# SCK_DATA_BOARD_2_1.net
KiCad netlist of a schematic drawn in EAGLE
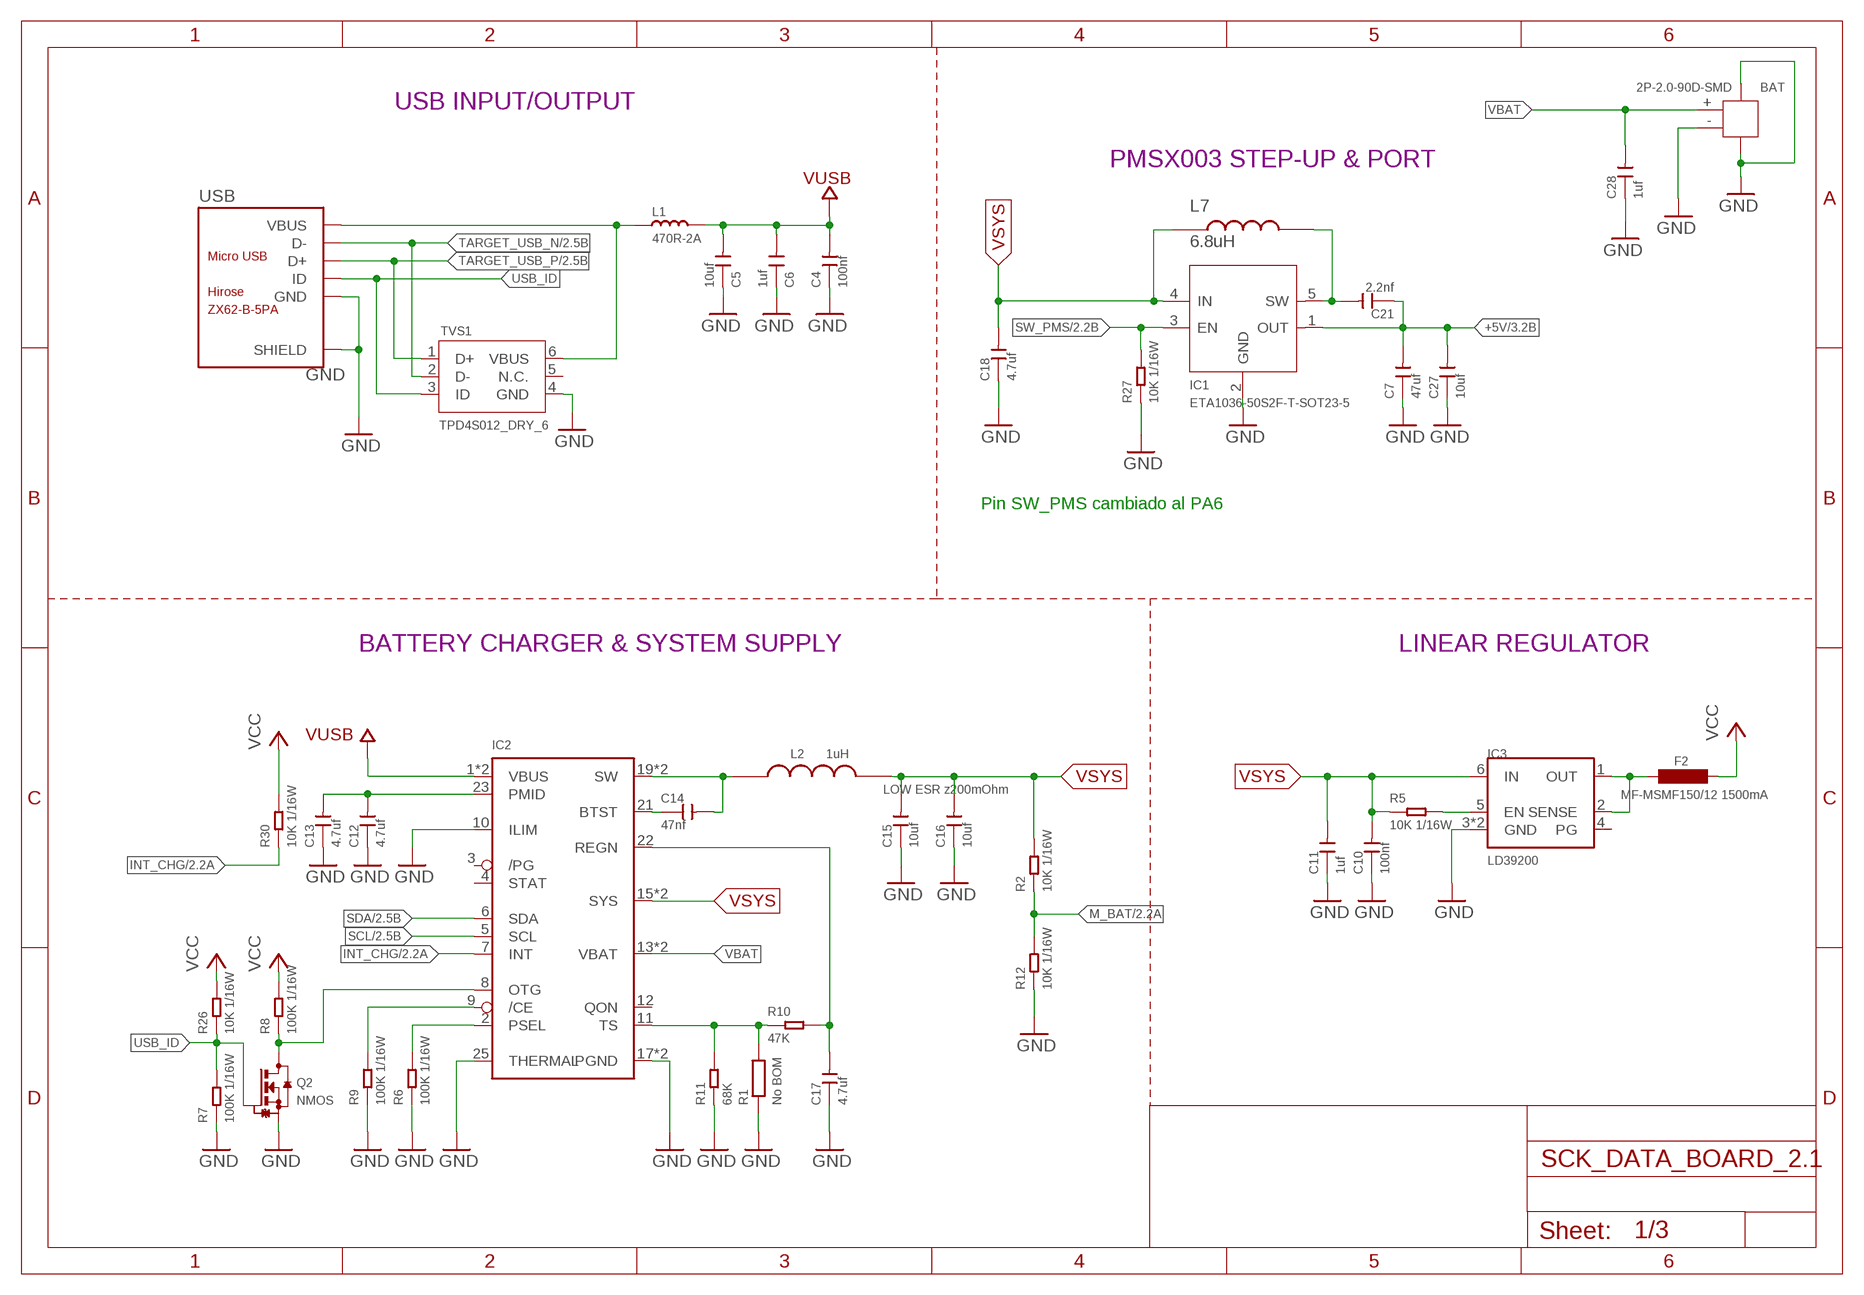
[diagram p0: schematic, sheet 1]
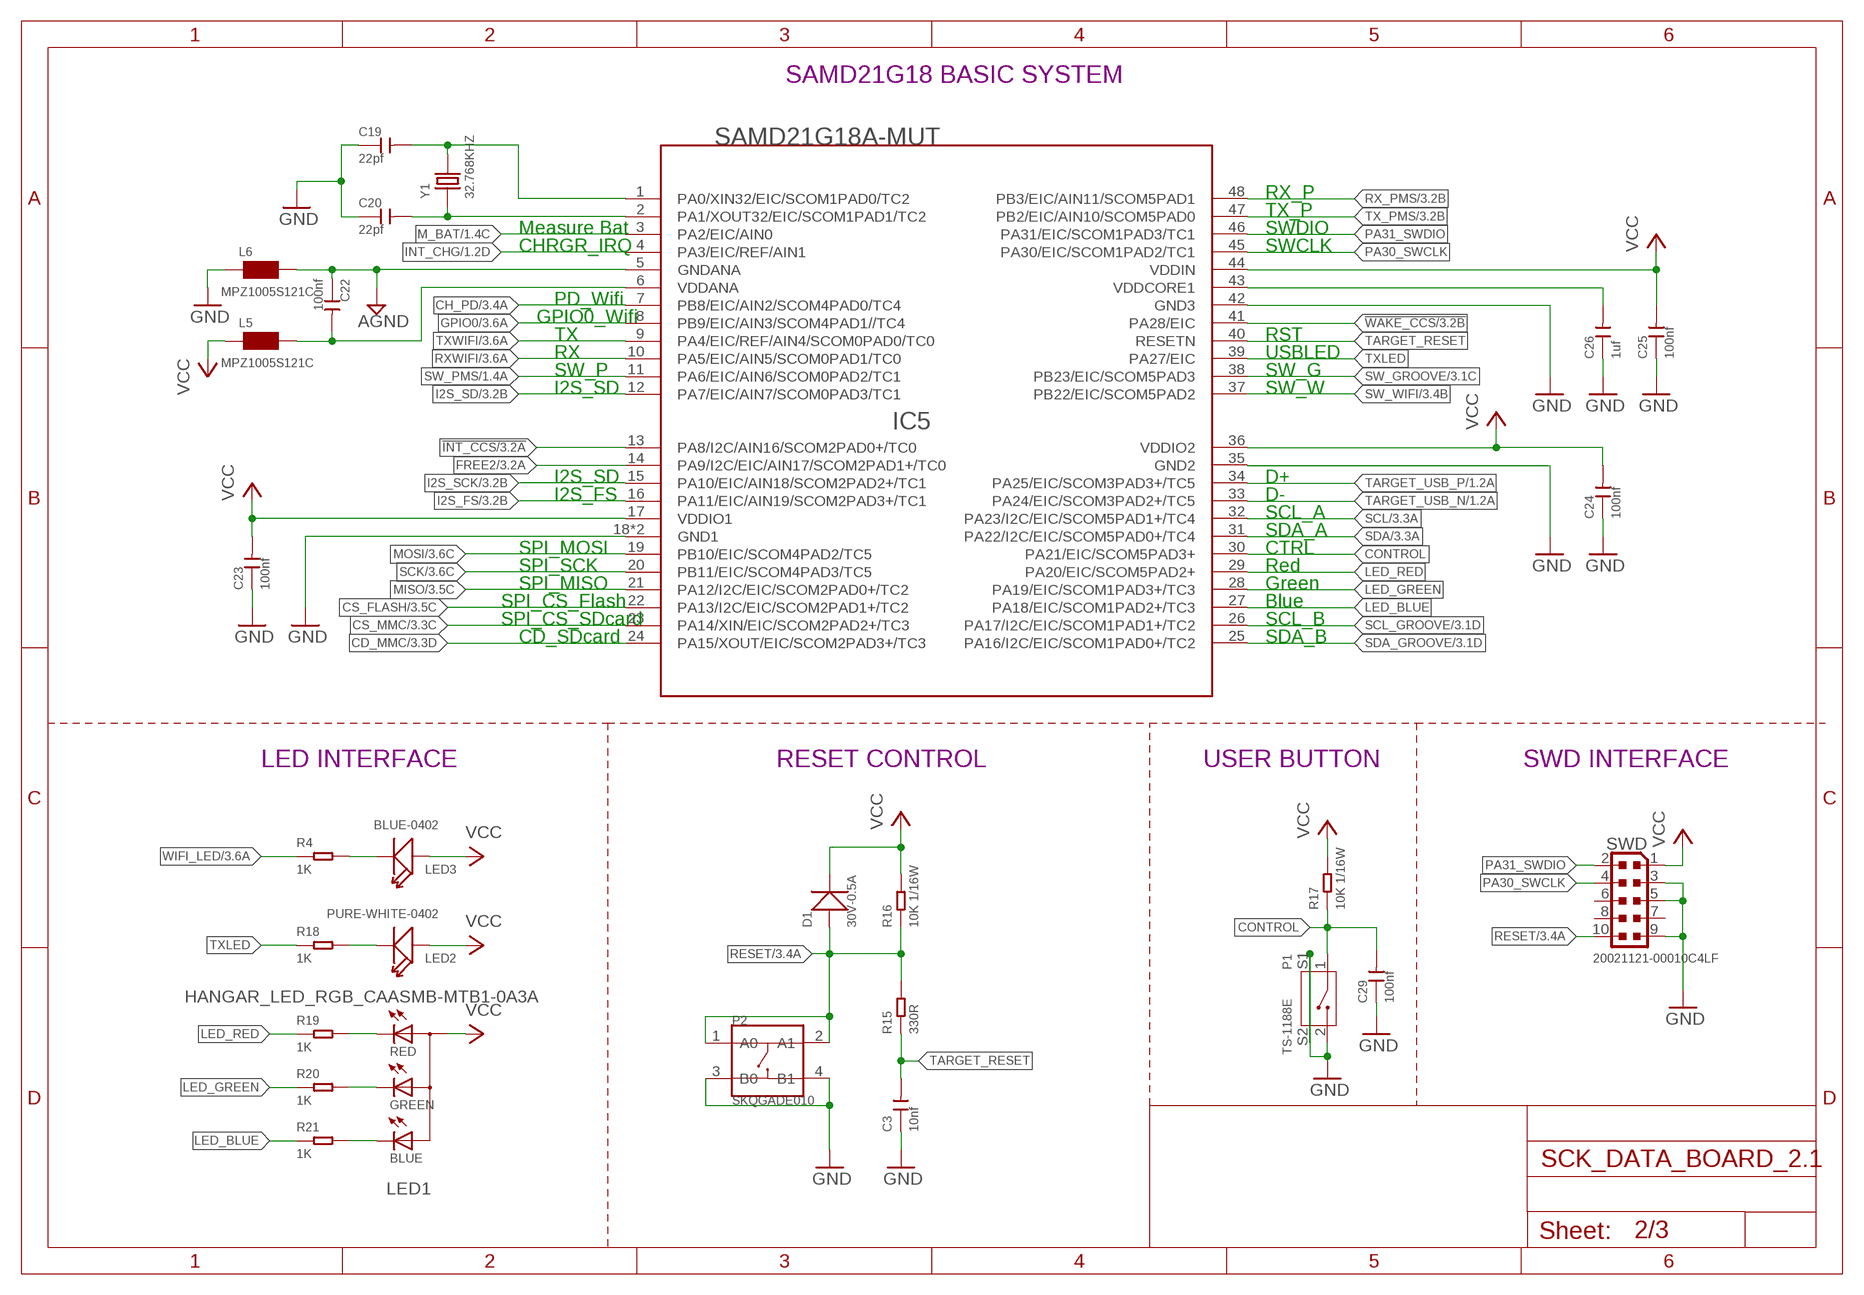
[diagram p1: schematic, sheet 2]
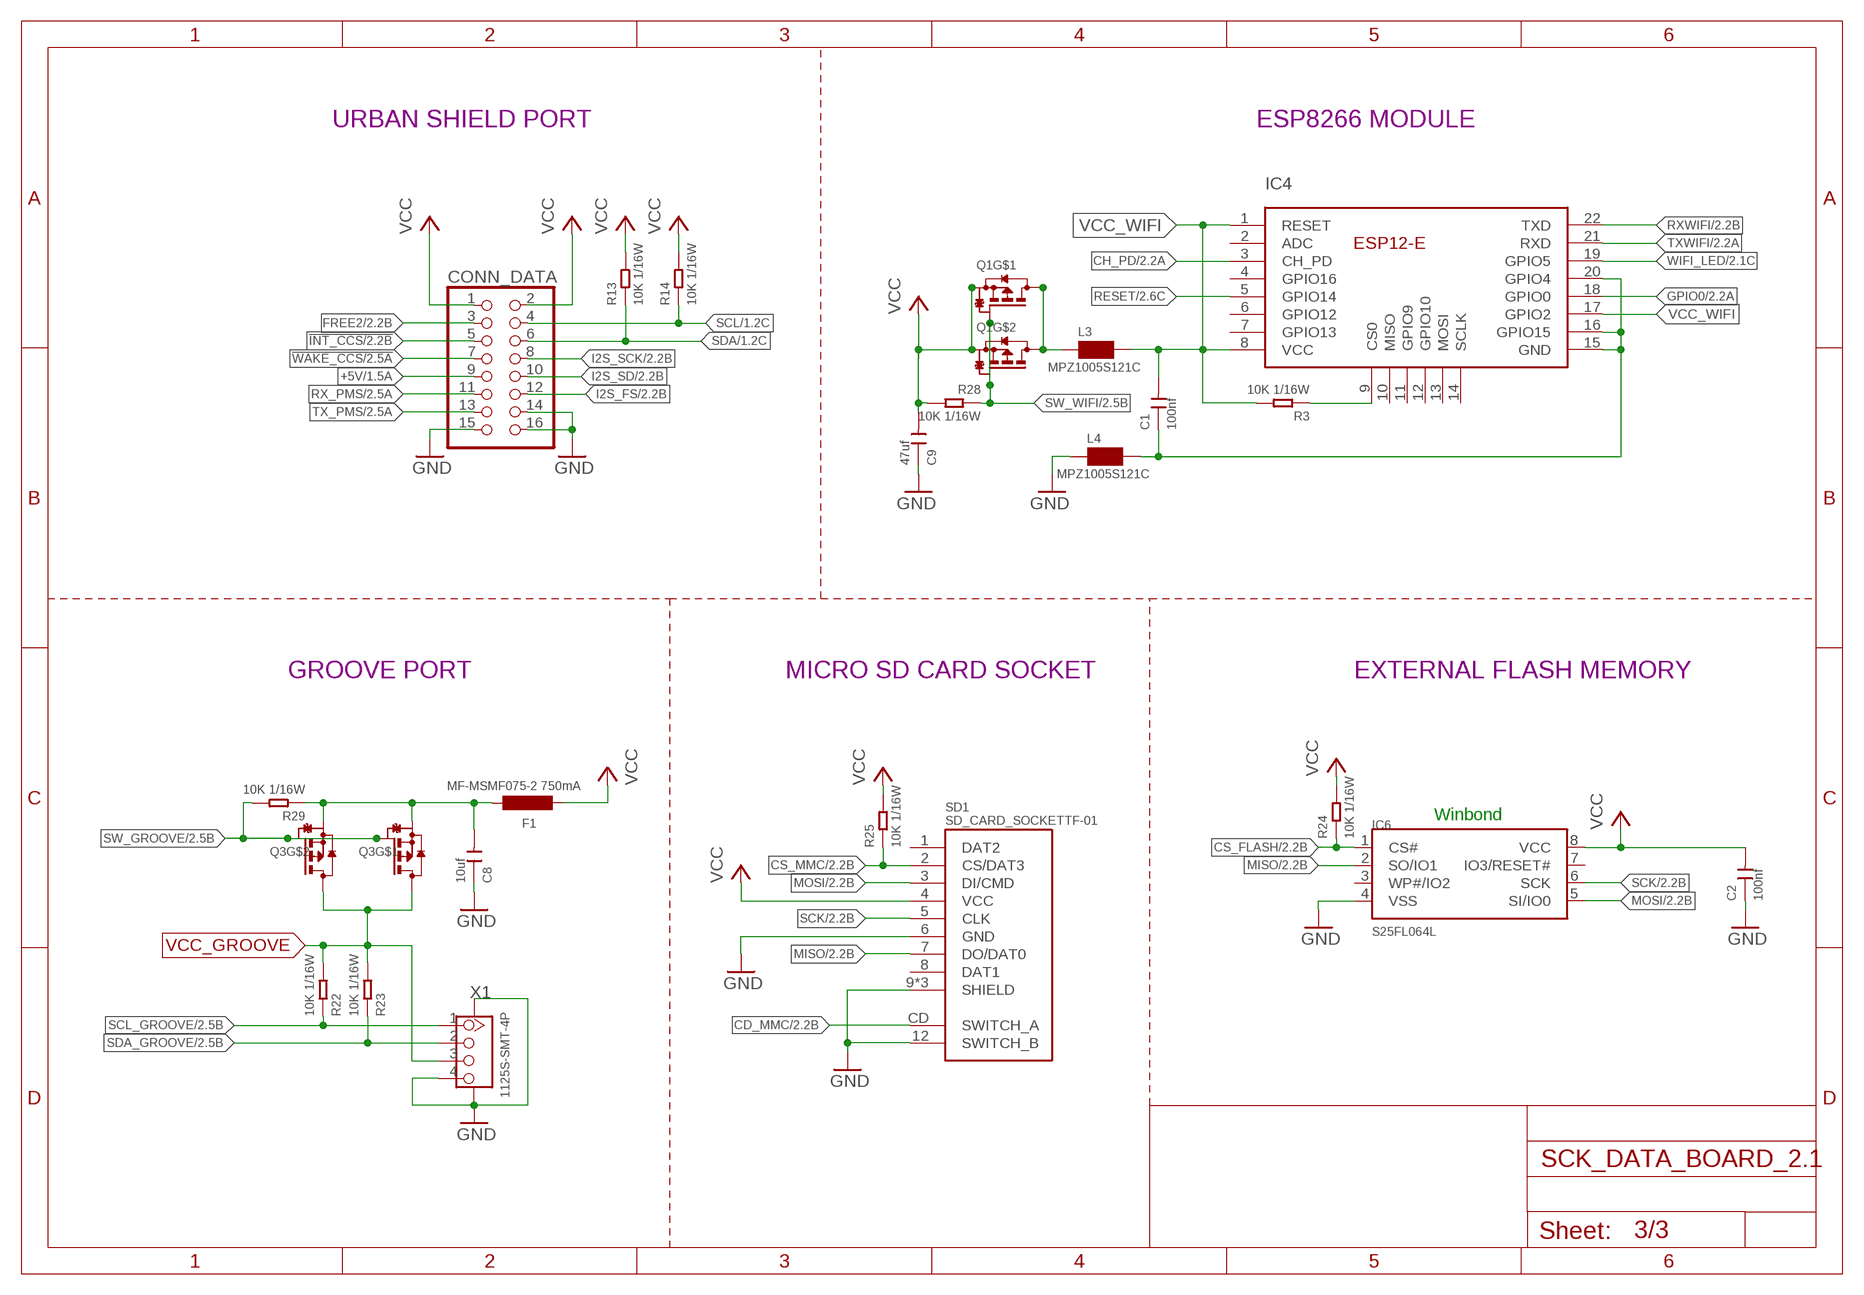
[diagram p2: schematic, sheet 3]

(export (version "E")
  (design (tool "Eeschema 10.0.6"))
  (components
    (comp (ref "BAT")
      (value "2P-2.0-90D-SMD")
      (footprint "eagle-import:HW2-SMD-2.0-90D")
      (libsource (lib "eagle-import") (part "CONN-HEADER-SMD-PH-SIDE-(2P-2.0MM)"))
    )
    (comp (ref "C4")
      (value "100nf")
      (footprint "eagle-import:C0402")
      (fields (field (name "MPN") "CC0402KRX7R8BB104"))
      (libsource (lib "eagle-import") (part "CERAMIC-100NF-25V-10%-X7R(0402)"))
    )
    (comp (ref "C5")
      (value "10uf")
      (footprint "eagle-import:C1206")
      (fields (field (name "MPN") "CC1206KKX5R8BB106"))
      (libsource (lib "eagle-import") (part "CERAMIC-10UF-25V-10%-X5R(1206)"))
    )
    (comp (ref "C6")
      (value "1uf")
      (footprint "eagle-import:C0805")
      (fields (field (name "MPN") "CC0805KKX7R8BB105"))
      (libsource (lib "eagle-import") (part "CERAMIC-1UF-25V-10%-X7R(0805)"))
    )
    (comp (ref "C7")
      (value "47uf")
      (footprint "eagle-import:C0805")
      (fields (field (name "MPN") "CC0805MKX5R5BB476"))
      (libsource (lib "eagle-import") (part "CERAMIC-47UF-6.3V-20%-X5R(0805)"))
    )
    (comp (ref "C10")
      (value "100nf")
      (footprint "eagle-import:C0402")
      (fields (field (name "MPN") "CC0402KRX7R8BB104"))
      (libsource (lib "eagle-import") (part "CERAMIC-100NF-25V-10%-X7R(0402)"))
    )
    (comp (ref "C11")
      (value "1uf")
      (footprint "eagle-import:C0805")
      (fields (field (name "MPN") "CC0805KKX7R8BB105"))
      (libsource (lib "eagle-import") (part "CERAMIC-1UF-25V-10%-X7R(0805)"))
    )
    (comp (ref "C12")
      (value "4.7uf")
      (footprint "eagle-import:C0603")
      (fields (field (name "MPN") "CC0603KRX5R6BB475"))
      (libsource (lib "eagle-import") (part "CERAMIC-4.7UF-10V-10%-X5R(0603)"))
    )
    (comp (ref "C13")
      (value "4.7uf")
      (footprint "eagle-import:C0603")
      (fields (field (name "MPN") "CC0603KRX5R6BB475"))
      (libsource (lib "eagle-import") (part "CERAMIC-4.7UF-10V-10%-X5R(0603)"))
    )
    (comp (ref "C14")
      (value "47nf")
      (footprint "eagle-import:C0402")
      (fields (field (name "MPN") "CC0402KRX7R8BB473"))
      (libsource (lib "eagle-import") (part "CERAMIC-47NF-25V-10%-X7R(0402)"))
    )
    (comp (ref "C15")
      (value "10uf")
      (footprint "eagle-import:C0603")
      (fields (field (name "MPN") "CC0603KRX5R6BB106"))
      (libsource (lib "eagle-import") (part "Seeed-OPL-Capacitor_CERAMIC-10UF-10V-10%-X5R(0603)"))
    )
    (comp (ref "C16")
      (value "10uf")
      (footprint "eagle-import:C0603")
      (fields (field (name "MPN") "CC0603KRX5R6BB106"))
      (libsource (lib "eagle-import") (part "Seeed-OPL-Capacitor_CERAMIC-10UF-10V-10%-X5R(0603)"))
    )
    (comp (ref "C17")
      (value "4.7uf")
      (footprint "eagle-import:C0603")
      (fields (field (name "MPN") "CC0603KRX5R6BB475"))
      (libsource (lib "eagle-import") (part "CERAMIC-4.7UF-10V-10%-X5R(0603)"))
    )
    (comp (ref "C18")
      (value "4.7uf")
      (footprint "eagle-import:C0603")
      (fields (field (name "MPN") "CC0603KRX5R6BB475"))
      (libsource (lib "eagle-import") (part "CERAMIC-4.7UF-10V-10%-X5R(0603)"))
    )
    (comp (ref "C21")
      (value "2.2nf")
      (footprint "eagle-import:C0402")
      (fields (field (name "MPN") "CC0402KRX7R9BB222"))
      (libsource (lib "eagle-import") (part "CERAMIC-2.2NF-50V-10%-X7R(0402)"))
    )
    (comp (ref "C27")
      (value "10uf")
      (footprint "eagle-import:C0603")
      (fields (field (name "MPN") "CC0603KRX5R6BB106"))
      (libsource (lib "eagle-import") (part "CERAMIC-10UF-10V-10%-X5R(0603)"))
    )
    (comp (ref "C28")
      (value "1uf")
      (footprint "eagle-import:C0805")
      (fields (field (name "MPN") "CC0805KKX7R8BB105"))
      (libsource (lib "eagle-import") (part "CERAMIC-1UF-25V-10%-X7R(0805)"))
    )
    (comp (ref "F2")
      (value "MF-MSMF150/12 1500mA")
      (footprint "eagle-import:L1812")
      (libsource (lib "eagle-import") (part "L-EUL1812"))
    )
    (comp (ref "IC1")
      (value "ETA1036-50S2F-T-SOT23-5")
      (footprint "eagle-import:SOT-23-5")
      (fields (field (name "MPN") "ETA1036-50S2F-T"))
      (libsource (lib "eagle-import") (part "PMIC-ETA1036-50S2F-T(SOT23-5)"))
    )
    (comp (ref "IC2")
      (value "BQ24259_VQFN(24)")
      (footprint "eagle-import:24-PIN_VQFN_THPAD")
      (libsource (lib "eagle-import") (part "BQ24259_VQFN(24)"))
    )
    (comp (ref "IC3")
      (value "LD39200")
      (footprint "eagle-import:DFN6_3X3MM")
      (libsource (lib "eagle-import") (part "LD39200"))
    )
    (comp (ref "L1")
      (value "470R-2A")
      (footprint "eagle-import:L0805")
      (fields (field (name "MPN") "WLB2012-471T20"))
      (libsource (lib "eagle-import") (part "SMD-FERRITE-BEAD-470R-2A(0805)'0805'"))
    )
    (comp (ref "L2")
      (value "1uH")
      (footprint "eagle-import:HANGAR_C1210")
      (libsource (lib "eagle-import") (part "LQH32PN1R0NNCL"))
    )
    (comp (ref "L7")
      (value "6.8uH")
      (footprint "eagle-import:IND_BOURNS_SRN3015TA_3X3_SMD")
      (libsource (lib "eagle-import") (part "RCL_L_SMD_SRN3015TA-6R8M"))
    )
    (comp (ref "Q2")
      (value "NMOS")
      (footprint "eagle-import:NMOS_UMT3")
      (libsource (lib "eagle-import") (part "NMOS_RJU003N03FRAT106"))
    )
    (comp (ref "R1")
      (value "No BOM")
      (footprint "eagle-import:HANGAR_R0402")
      (libsource (lib "eagle-import") (part "HANGAR_R-EU_R0402"))
    )
    (comp (ref "R2")
      (value "10K 1/16W")
      (footprint "eagle-import:R0402")
      (fields (field (name "MPN") "RC0402FR-0710KL"))
      (libsource (lib "eagle-import") (part "SMD-RES-10K-1%-1/16W(0402)"))
    )
    (comp (ref "R5")
      (value "10K 1/16W")
      (footprint "eagle-import:R0402")
      (fields (field (name "MPN") "RC0402FR-0710KL"))
      (libsource (lib "eagle-import") (part "SMD-RES-10K-1%-1/16W(0402)"))
    )
    (comp (ref "R6")
      (value "100K 1/16W")
      (footprint "eagle-import:R0402")
      (fields (field (name "MPN") "RC0402JR-07100KL"))
      (libsource (lib "eagle-import") (part "SMD-RES-100K-5%-1/16W(0402)"))
    )
    (comp (ref "R7")
      (value "100K 1/16W")
      (footprint "eagle-import:R0402")
      (fields (field (name "MPN") "RC0402JR-07100KL"))
      (libsource (lib "eagle-import") (part "SMD-RES-100K-5%-1/16W(0402)"))
    )
    (comp (ref "R8")
      (value "100K 1/16W")
      (footprint "eagle-import:R0402")
      (fields (field (name "MPN") "RC0402JR-07100KL"))
      (libsource (lib "eagle-import") (part "SMD-RES-100K-5%-1/16W(0402)"))
    )
    (comp (ref "R9")
      (value "100K 1/16W")
      (footprint "eagle-import:R0402")
      (fields (field (name "MPN") "RC0402JR-07100KL"))
      (libsource (lib "eagle-import") (part "SMD-RES-100K-5%-1/16W(0402)"))
    )
    (comp (ref "R10")
      (value "47K")
      (footprint "eagle-import:R0402")
      (fields (field (name "MPN") "RC0402JR-0747KL"))
      (libsource (lib "eagle-import") (part "SMD-RES-47K-5%-1/16W(0402)"))
    )
    (comp (ref "R11")
      (value "68K")
      (footprint "eagle-import:R0402")
      (fields (field (name "MPN") "RC0402JR-0768KL"))
      (libsource (lib "eagle-import") (part "SMD-RES-68K-50V-5%(0402)"))
    )
    (comp (ref "R12")
      (value "10K 1/16W")
      (footprint "eagle-import:R0402")
      (fields (field (name "MPN") "RC0402FR-0710KL"))
      (libsource (lib "eagle-import") (part "SMD-RES-10K-1%-1/16W(0402)"))
    )
    (comp (ref "R26")
      (value "10K 1/16W")
      (footprint "eagle-import:R0402")
      (fields (field (name "MPN") "RC0402FR-0710KL"))
      (libsource (lib "eagle-import") (part "SMD-RES-10K-1%-1/16W(0402)"))
    )
    (comp (ref "R27")
      (value "10K 1/16W")
      (footprint "eagle-import:R0402")
      (fields (field (name "MPN") "RC0402FR-0710KL"))
      (libsource (lib "eagle-import") (part "Seeed-Resistor_SMD-RES-10K-1%-1/16W(0402)"))
    )
    (comp (ref "R30")
      (value "10K 1/16W")
      (footprint "eagle-import:R0402")
      (fields (field (name "MPN") "RC0402FR-0710KL"))
      (libsource (lib "eagle-import") (part "SMD-RES-10K-1%-1/16W(0402)"))
    )
    (comp (ref "TVS1")
      (value "TPD4S012_DRY_6")
      (footprint "eagle-import:DRY6")
      (libsource (lib "eagle-import") (part "TPD4S012_DRY_6"))
    )
    (comp (ref "USB")
      (value "ZX62-B-5PA")
      (footprint "eagle-import:MICRO-USB5+6P-SMD-0.65-AB")
      (libsource (lib "eagle-import") (part "MICRO-USB-SMD(ZX62-B-5PA)"))
    )
    (comp (ref "C1")
      (value "100nf")
      (footprint "eagle-import:C0402")
      (fields (field (name "MPN") "CC0402KRX7R8BB104"))
      (libsource (lib "eagle-import") (part "CERAMIC-100NF-25V-10%-X7R(0402)"))
    )
    (comp (ref "C2")
      (value "100nf")
      (footprint "eagle-import:C0402")
      (fields (field (name "MPN") "CC0402KRX7R8BB104"))
      (libsource (lib "eagle-import") (part "CERAMIC-100NF-25V-10%-X7R(0402)"))
    )
    (comp (ref "C8")
      (value "10uf")
      (footprint "eagle-import:C1206")
      (fields (field (name "MPN") "CC1206KKX5R8BB106"))
      (libsource (lib "eagle-import") (part "CERAMIC-10UF-25V-10%-X5R(1206)"))
    )
    (comp (ref "C9")
      (value "47uf")
      (footprint "eagle-import:C1210")
      (fields (field (name "MPN") "GRM32ER71A476ME15L"))
      (libsource (lib "eagle-import") (part "CERAMIC-47UF-10V-20%-X7R(1210)"))
    )
    (comp (ref "CONN_DATA")
      (value "PINHD_2X8FEM_SMD")
      (footprint "eagle-import:PINHD_2X8_SMD_FEMALE_UNHOLED")
      (libsource (lib "eagle-import") (part "PINHD_2X8FEM_SMD"))
    )
    (comp (ref "F1")
      (value "MF-MSMF075-2 750mA")
      (footprint "eagle-import:L1812")
      (libsource (lib "eagle-import") (part "L-EUL1812"))
    )
    (comp (ref "IC4")
      (value "HANGAR_ESP-12-E")
      (footprint "eagle-import:HANGAR_ESP12-E")
      (libsource (lib "eagle-import") (part "HANGAR_ESP-12-E"))
    )
    (comp (ref "IC6")
      (value "S25FL064L")
      (footprint "eagle-import:SOIC_8-208MILS")
      (libsource (lib "eagle-import") (part "FLASH_S25FL064L"))
    )
    (comp (ref "L3")
      (value "MPZ1005S121C")
      (footprint "eagle-import:0402")
      (libsource (lib "eagle-import") (part "WE-CBF_0402"))
    )
    (comp (ref "L4")
      (value "MPZ1005S121C")
      (footprint "eagle-import:0402")
      (libsource (lib "eagle-import") (part "WE-CBF_0402"))
    )
    (comp (ref "Q1")
      (value "PMOS")
      (footprint "eagle-import:HANGAR_POWERPAKSC70-6L")
      (fields (field (name "MPN") "SIA923AEDJ-T1-GE3 "))
      (libsource (lib "eagle-import") (part "MOSFETP_BOTH"))
    )
    (comp (ref "Q3")
      (value "PMOS")
      (footprint "eagle-import:HANGAR_POWERPAKSC70-6L")
      (libsource (lib "eagle-import") (part "MOSFETP_BOTH"))
    )
    (comp (ref "R3")
      (value "10K 1/16W")
      (footprint "eagle-import:R0402")
      (fields (field (name "MPN") "RC0402FR-0710KL"))
      (libsource (lib "eagle-import") (part "SMD-RES-10K-1%-1/16W(0402)"))
    )
    (comp (ref "R13")
      (value "10K 1/16W")
      (footprint "eagle-import:R0402")
      (fields (field (name "MPN") "RC0402FR-0710KL"))
      (libsource (lib "eagle-import") (part "SMD-RES-10K-1%-1/16W(0402)"))
    )
    (comp (ref "R14")
      (value "10K 1/16W")
      (footprint "eagle-import:R0402")
      (fields (field (name "MPN") "RC0402FR-0710KL"))
      (libsource (lib "eagle-import") (part "SMD-RES-10K-1%-1/16W(0402)"))
    )
    (comp (ref "R22")
      (value "10K 1/16W")
      (footprint "eagle-import:R0402")
      (fields (field (name "MPN") "RC0402FR-0710KL"))
      (libsource (lib "eagle-import") (part "SMD-RES-10K-1%-1/16W(0402)"))
    )
    (comp (ref "R23")
      (value "10K 1/16W")
      (footprint "eagle-import:R0402")
      (fields (field (name "MPN") "RC0402FR-0710KL"))
      (libsource (lib "eagle-import") (part "SMD-RES-10K-1%-1/16W(0402)"))
    )
    (comp (ref "R24")
      (value "10K 1/16W")
      (footprint "eagle-import:R0402")
      (fields (field (name "MPN") "RC0402FR-0710KL"))
      (libsource (lib "eagle-import") (part "SMD-RES-10K-1%-1/16W(0402)"))
    )
    (comp (ref "R25")
      (value "10K 1/16W")
      (footprint "eagle-import:R0402")
      (fields (field (name "MPN") "RC0402FR-0710KL"))
      (libsource (lib "eagle-import") (part "SMD-RES-10K-1%-1/16W(0402)"))
    )
    (comp (ref "R28")
      (value "10K 1/16W")
      (footprint "eagle-import:R0402")
      (fields (field (name "MPN") "RC0402FR-0710KL"))
      (libsource (lib "eagle-import") (part "Seeed-Resistor_SMD-RES-10K-1%-1/16W(0402)"))
    )
    (comp (ref "R29")
      (value "10K 1/16W")
      (footprint "eagle-import:R0402")
      (fields (field (name "MPN") "RC0402FR-0710KL"))
      (libsource (lib "eagle-import") (part "Seeed-Resistor_SMD-RES-10K-1%-1/16W(0402)"))
    )
    (comp (ref "SD1")
      (value "SD_CARD_SOCKETTF-01")
      (footprint "eagle-import:TF-01")
      (fields (field (name "MPN") "320090008"))
      (libsource (lib "eagle-import") (part "SD_CARD_SOCKETTF-01"))
    )
    (comp (ref "X1")
      (value "1125S-SMT-4P")
      (footprint "eagle-import:HW4-SMD-2.0")
      (fields (field (name "MPN") "320110030"))
      (libsource (lib "eagle-import") (part "GROVE-CONNECTOR-SMD'DD'"))
    )
    (comp (ref "C3")
      (value "10nf")
      (footprint "eagle-import:C0402")
      (fields (field (name "MPN") "CC0402KRX7R9BB103"))
      (libsource (lib "eagle-import") (part "CERAMIC-10NF-50V-10%-X7R(0402)"))
    )
    (comp (ref "C19")
      (value "22pf")
      (footprint "eagle-import:C0402")
      (fields (field (name "MPN") "CC0402JRNPO9BN220"))
      (libsource (lib "eagle-import") (part "CERAMIC-22PF-50V-5%-NPO(0402)"))
    )
    (comp (ref "C20")
      (value "22pf")
      (footprint "eagle-import:C0402")
      (fields (field (name "MPN") "CC0402JRNPO9BN220"))
      (libsource (lib "eagle-import") (part "CERAMIC-22PF-50V-5%-NPO(0402)"))
    )
    (comp (ref "C22")
      (value "100nf")
      (footprint "eagle-import:C0402")
      (fields (field (name "MPN") "CC0402KRX7R8BB104"))
      (libsource (lib "eagle-import") (part "CERAMIC-100NF-25V-10%-X7R(0402)"))
    )
    (comp (ref "C23")
      (value "100nf")
      (footprint "eagle-import:C0402")
      (fields (field (name "MPN") "CC0402KRX7R8BB104"))
      (libsource (lib "eagle-import") (part "CERAMIC-100NF-25V-10%-X7R(0402)"))
    )
    (comp (ref "C24")
      (value "100nf")
      (footprint "eagle-import:C0402")
      (fields (field (name "MPN") "CC0402KRX7R8BB104"))
      (libsource (lib "eagle-import") (part "CERAMIC-100NF-25V-10%-X7R(0402)"))
    )
    (comp (ref "C25")
      (value "100nf")
      (footprint "eagle-import:C0402")
      (fields (field (name "MPN") "CC0402KRX7R8BB104"))
      (libsource (lib "eagle-import") (part "CERAMIC-100NF-25V-10%-X7R(0402)"))
    )
    (comp (ref "C26")
      (value "1uf")
      (footprint "eagle-import:C0805")
      (fields (field (name "MPN") "CC0805KKX7R8BB105"))
      (libsource (lib "eagle-import") (part "CERAMIC-1UF-25V-10%-X7R(0805)"))
    )
    (comp (ref "C29")
      (value "100nf")
      (footprint "eagle-import:C0402")
      (fields (field (name "MPN") "CC0402KRX7R8BB104"))
      (libsource (lib "eagle-import") (part "CERAMIC-100NF-25V-10%-X7R(0402)"))
    )
    (comp (ref "D1")
      (value "30V-0.5A")
      (footprint "eagle-import:SOD-323")
      (fields (field (name "MPN") "LRB551V-30T1G"))
      (libsource (lib "eagle-import") (part "SMD-DIODE-SCHOTTKY-30V-0.5A(SOD-323)"))
    )
    (comp (ref "IC5")
      (value "SAMD21G18A-MUT")
      (footprint "eagle-import:HANGAR_QFN48-7X7")
      (libsource (lib "eagle-import") (part "HANGAR_SAMD21G18A-MUT"))
    )
    (comp (ref "L5")
      (value "MPZ1005S121C")
      (footprint "eagle-import:0402")
      (libsource (lib "eagle-import") (part "WE-CBF_0402"))
    )
    (comp (ref "L6")
      (value "MPZ1005S121C")
      (footprint "eagle-import:0402")
      (libsource (lib "eagle-import") (part "WE-CBF_0402"))
    )
    (comp (ref "LED1")
      (value "HANGAR_LED_RGB_CAASMB-MTB1-0A3A")
      (footprint "eagle-import:HANGAR_P-LCC-4")
      (libsource (lib "eagle-import") (part "HANGAR_LED_RGB_CAASMB-MTB1-0A3A"))
    )
    (comp (ref "LED2")
      (value "PURE-WHITE-0402")
      (footprint "eagle-import:LED-0402")
      (fields (field (name "MPN") "16-219A/T2D-AR2T1QY/3T"))
      (libsource (lib "eagle-import") (part "SMD-LED-YELLOW-DIFFUSED-PURE-WHITE(0402)"))
    )
    (comp (ref "LED3")
      (value "BLUE-0402")
      (footprint "eagle-import:LED-0402")
      (fields (field (name "MPN") "BL-HB337A-AV-TRB"))
      (libsource (lib "eagle-import") (part "SMD-LED-CLEAR-BLUE(0402)"))
    )
    (comp (ref "P1")
      (value "TS-1188E")
      (footprint "eagle-import:SW4-SMD-7.0X3.5X3.5MM-90D")
      (libsource (lib "eagle-import") (part "SMD-BUTTON(2+2P-7X3.5MM-90D)"))
    )
    (comp (ref "P2")
      (value "SKQGADE010")
      (footprint "eagle-import:SW4-SMD-5.2X5.2X1.5MM")
      (libsource (lib "eagle-import") (part "SMD-BUTTON(4P-5.2X5.2X1.5MM-SKQGADE010)-SKQGADE010"))
    )
    (comp (ref "R4")
      (value "1K")
      (footprint "eagle-import:R0402")
      (fields (field (name "MPN") "RC0402JR-071KL"))
      (libsource (lib "eagle-import") (part "SMD-RES-1K-5%-1/16W(0402)"))
    )
    (comp (ref "R15")
      (value "330R")
      (footprint "eagle-import:R0402")
      (fields (field (name "MPN") "RC0402FR-07330RL"))
      (libsource (lib "eagle-import") (part "SMD-RES-330R-1%-1/16W(0402)"))
    )
    (comp (ref "R16")
      (value "10K 1/16W")
      (footprint "eagle-import:R0402")
      (fields (field (name "MPN") "RC0402FR-0710KL"))
      (libsource (lib "eagle-import") (part "SMD-RES-10K-1%-1/16W(0402)"))
    )
    (comp (ref "R17")
      (value "10K 1/16W")
      (footprint "eagle-import:R0402")
      (fields (field (name "MPN") "RC0402FR-0710KL"))
      (libsource (lib "eagle-import") (part "SMD-RES-10K-1%-1/16W(0402)"))
    )
    (comp (ref "R18")
      (value "1K")
      (footprint "eagle-import:R0402")
      (fields (field (name "MPN") "RC0402JR-071KL"))
      (libsource (lib "eagle-import") (part "SMD-RES-1K-5%-1/16W(0402)"))
    )
    (comp (ref "R19")
      (value "1K")
      (footprint "eagle-import:R0402")
      (fields (field (name "MPN") "RC0402JR-071KL"))
      (libsource (lib "eagle-import") (part "SMD-RES-1K-5%-1/16W(0402)"))
    )
    (comp (ref "R20")
      (value "1K")
      (footprint "eagle-import:R0402")
      (fields (field (name "MPN") "RC0402JR-071KL"))
      (libsource (lib "eagle-import") (part "SMD-RES-1K-5%-1/16W(0402)"))
    )
    (comp (ref "R21")
      (value "1K")
      (footprint "eagle-import:R0402")
      (fields (field (name "MPN") "RC0402JR-071KL"))
      (libsource (lib "eagle-import") (part "SMD-RES-1K-5%-1/16W(0402)"))
    )
    (comp (ref "SWD")
      (value "20021121-00010C4LF")
      (footprint "eagle-import:2X05_SMD_1.27MM")
      (libsource (lib "eagle-import") (part "PINHEAD_PINHD-2X5SMD"))
    )
    (comp (ref "Y1")
      (value "32.768KHZ")
      (footprint "eagle-import:X2-SMD-3.2X1.5X0.55MM")
      (fields (field (name "MPN") "FC-135"))
      (libsource (lib "eagle-import") (part "SMD-CRYSTAL-ABS07-32.768KHZ-7PF-20PPM-70K(2P-3.2X1.5MM)"))
    )
  )
  (nets
    (net (code "1") (name "+5V") (class "Default")
      (node (ref "C21") (pin "1") (pinfunction "1_1") (pintype "passive"))
      (node (ref "C27") (pin "2") (pinfunction "2_2") (pintype "passive"))
      (node (ref "C7") (pin "2") (pinfunction "2_2") (pintype "passive"))
      (node (ref "CONN_DATA") (pin "9") (pinfunction "9_9") (pintype "passive"))
      (node (ref "IC1") (pin "1") (pinfunction "OUT_1") (pintype "bidirectional"))
    )
    (net (code "2") (name "AGND") (class "Default")
      (node (ref "C22") (pin "1") (pinfunction "1_1") (pintype "passive"))
      (node (ref "IC5") (pin "5") (pinfunction "GNDANA_5") (pintype "power_in"))
      (node (ref "L6") (pin "2") (pinfunction "2_2") (pintype "passive"))
    )
    (net (code "3") (name "CD_MMC") (class "Default")
      (node (ref "IC5") (pin "24") (pinfunction "PA15/XOUT/EIC/SCOM2PAD3+/TC3_24") (pintype "bidirectional"))
      (node (ref "SD1") (pin "CD") (pinfunction "SWITCH_A_CD") (pintype "bidirectional"))
    )
    (net (code "4") (name "CH_PD") (class "Default")
      (node (ref "IC4") (pin "3") (pinfunction "CH_PD_3") (pintype "input"))
      (node (ref "IC5") (pin "7") (pinfunction "PB8/EIC/AIN2/SCOM4PAD0/TC4_7") (pintype "bidirectional"))
    )
    (net (code "5") (name "CONTROL") (class "Default")
      (node (ref "C29") (pin "2") (pinfunction "2_2") (pintype "passive"))
      (node (ref "IC5") (pin "30") (pinfunction "PA21/EIC/SCOM5PAD3+_30") (pintype "bidirectional"))
      (node (ref "P1") (pin "1") (pinfunction "1_1") (pintype "bidirectional"))
      (node (ref "R17") (pin "1") (pinfunction "1_1") (pintype "passive"))
    )
    (net (code "6") (name "CS_FLASH") (class "Default")
      (node (ref "IC5") (pin "22") (pinfunction "PA13/I2C/EIC/SCOM2PAD1+/TC2_22") (pintype "bidirectional"))
      (node (ref "IC6") (pin "1") (pinfunction "CS#_1") (pintype "bidirectional"))
      (node (ref "R24") (pin "1") (pinfunction "1_1") (pintype "passive"))
    )
    (net (code "7") (name "CS_MMC") (class "Default")
      (node (ref "IC5") (pin "23") (pinfunction "PA14/XIN/EIC/SCOM2PAD2+/TC3_23") (pintype "bidirectional"))
      (node (ref "R25") (pin "1") (pinfunction "1_1") (pintype "passive"))
      (node (ref "SD1") (pin "2") (pinfunction "CS/DAT3_2") (pintype "bidirectional"))
    )
    (net (code "8") (name "FREE2") (class "Default")
      (node (ref "CONN_DATA") (pin "3") (pinfunction "3_3") (pintype "passive"))
      (node (ref "IC5") (pin "14") (pinfunction "PA9/I2C/EIC/AIN17/SCOM2PAD1+/TC0_14") (pintype "bidirectional"))
    )
    (net (code "9") (name "GND") (class "Default")
      (node (ref "BAT") (pin "-") (pinfunction "2_-") (pintype "bidirectional"))
      (node (ref "BAT") (pin "3") (pinfunction "3_3") (pintype "bidirectional"))
      (node (ref "BAT") (pin "4") (pinfunction "4_4") (pintype "bidirectional"))
      (node (ref "C10") (pin "1") (pinfunction "1_1") (pintype "passive"))
      (node (ref "C11") (pin "1") (pinfunction "1_1") (pintype "passive"))
      (node (ref "C12") (pin "1") (pinfunction "1_1") (pintype "passive"))
      (node (ref "C13") (pin "1") (pinfunction "1_1") (pintype "passive"))
      (node (ref "C15") (pin "1") (pinfunction "1_1") (pintype "passive"))
      (node (ref "C16") (pin "1") (pinfunction "1_1") (pintype "passive"))
      (node (ref "C17") (pin "1") (pinfunction "1_1") (pintype "passive"))
      (node (ref "C18") (pin "1") (pinfunction "1_1") (pintype "passive"))
      (node (ref "C19") (pin "1") (pinfunction "1_1") (pintype "passive"))
      (node (ref "C2") (pin "1") (pinfunction "1_1") (pintype "passive"))
      (node (ref "C20") (pin "1") (pinfunction "1_1") (pintype "passive"))
      (node (ref "C23") (pin "1") (pinfunction "1_1") (pintype "passive"))
      (node (ref "C24") (pin "1") (pinfunction "1_1") (pintype "passive"))
      (node (ref "C25") (pin "1") (pinfunction "1_1") (pintype "passive"))
      (node (ref "C26") (pin "1") (pinfunction "1_1") (pintype "passive"))
      (node (ref "C27") (pin "1") (pinfunction "1_1") (pintype "passive"))
      (node (ref "C28") (pin "1") (pinfunction "1_1") (pintype "passive"))
      (node (ref "C29") (pin "1") (pinfunction "1_1") (pintype "passive"))
      (node (ref "C3") (pin "1") (pinfunction "1_1") (pintype "passive"))
      (node (ref "C4") (pin "1") (pinfunction "1_1") (pintype "passive"))
      (node (ref "C5") (pin "1") (pinfunction "1_1") (pintype "passive"))
      (node (ref "C6") (pin "1") (pinfunction "1_1") (pintype "passive"))
      (node (ref "C7") (pin "1") (pinfunction "1_1") (pintype "passive"))
      (node (ref "C8") (pin "1") (pinfunction "1_1") (pintype "passive"))
      (node (ref "C9") (pin "1") (pinfunction "1_1") (pintype "passive"))
      (node (ref "CONN_DATA") (pin "14") (pinfunction "14_14") (pintype "passive"))
      (node (ref "CONN_DATA") (pin "15") (pinfunction "15_15") (pintype "passive"))
      (node (ref "CONN_DATA") (pin "16") (pinfunction "16_16") (pintype "passive"))
      (node (ref "IC1") (pin "2") (pinfunction "GND_2") (pintype "bidirectional"))
      (node (ref "IC2") (pin "10") (pinfunction "ILIM_10") (pintype "bidirectional"))
      (node (ref "IC2") (pin "17") (pinfunction "PGND_17") (pintype "bidirectional"))
      (node (ref "IC2") (pin "18") (pinfunction "PGND_18") (pintype "bidirectional"))
      (node (ref "IC2") (pin "25") (pinfunction "THERMAL_25") (pintype "bidirectional"))
      (node (ref "IC3") (pin "3") (pinfunction "GND_3") (pintype "bidirectional"))
      (node (ref "IC3") (pin "7") (pinfunction "GND_7") (pintype "bidirectional"))
      (node (ref "IC5") (pin "18") (pinfunction "GND1_18") (pintype "power_in"))
      (node (ref "IC5") (pin "35") (pinfunction "GND2_35") (pintype "power_in"))
      (node (ref "IC5") (pin "42") (pinfunction "GND3_42") (pintype "power_in"))
      (node (ref "IC5") (pin "TP") (pinfunction "GND1_TP") (pintype "power_in"))
      (node (ref "IC6") (pin "4") (pinfunction "VSS_4") (pintype "bidirectional"))
      (node (ref "L4") (pin "2") (pinfunction "2_2") (pintype "passive"))
      (node (ref "L6") (pin "1") (pinfunction "1_1") (pintype "passive"))
      (node (ref "P1") (pin "2") (pinfunction "2_2") (pintype "bidirectional"))
      (node (ref "P1") (pin "S1") (pinfunction "S1_S1") (pintype "bidirectional"))
      (node (ref "P1") (pin "S2") (pinfunction "S2_S2") (pintype "bidirectional"))
      (node (ref "P2") (pin "3") (pinfunction "B0_3") (pintype "bidirectional"))
      (node (ref "P2") (pin "4") (pinfunction "B1_4") (pintype "bidirectional"))
      (node (ref "Q2") (pin "1") (pinfunction "S_1") (pintype "passive"))
      (node (ref "R1") (pin "1") (pinfunction "1_1") (pintype "passive"))
      (node (ref "R11") (pin "1") (pinfunction "1_1") (pintype "passive"))
      (node (ref "R12") (pin "1") (pinfunction "1_1") (pintype "passive"))
      (node (ref "R27") (pin "1") (pinfunction "1_1") (pintype "passive"))
      (node (ref "R6") (pin "1") (pinfunction "1_1") (pintype "passive"))
      (node (ref "R7") (pin "1") (pinfunction "1_1") (pintype "passive"))
      (node (ref "R9") (pin "1") (pinfunction "1_1") (pintype "passive"))
      (node (ref "SD1") (pin "10") (pinfunction "SHIELD_10") (pintype "bidirectional"))
      (node (ref "SD1") (pin "11") (pinfunction "SHIELD_11") (pintype "bidirectional"))
      (node (ref "SD1") (pin "12") (pinfunction "SWITCH_B_12") (pintype "bidirectional"))
      (node (ref "SD1") (pin "6") (pinfunction "GND_6") (pintype "bidirectional"))
      (node (ref "SD1") (pin "9") (pinfunction "SHIELD_9") (pintype "bidirectional"))
      (node (ref "SWD") (pin "3") (pinfunction "3_3") (pintype "passive"))
      (node (ref "SWD") (pin "5") (pinfunction "5_5") (pintype "passive"))
      (node (ref "SWD") (pin "9") (pinfunction "9_9") (pintype "passive"))
      (node (ref "TVS1") (pin "4") (pinfunction "GND_4") (pintype "passive"))
      (node (ref "USB") (pin "5") (pinfunction "GND_5") (pintype "power_in"))
      (node (ref "USB") (pin "P1") (pinfunction "SHIELD_P1") (pintype "power_in"))
      (node (ref "USB") (pin "P2") (pinfunction "SHIELD_P2") (pintype "power_in"))
      (node (ref "USB") (pin "P3") (pinfunction "SHIELD_P3") (pintype "power_in"))
      (node (ref "USB") (pin "P4") (pinfunction "SHIELD_P4") (pintype "power_in"))
      (node (ref "USB") (pin "P5") (pinfunction "SHIELD_P5") (pintype "power_in"))
      (node (ref "USB") (pin "P6") (pinfunction "SHIELD_P6") (pintype "power_in"))
      (node (ref "X1") (pin "4") (pinfunction "4_4") (pintype "bidirectional"))
      (node (ref "X1") (pin "SS1") (pinfunction "SS1_SS1") (pintype "bidirectional"))
      (node (ref "X1") (pin "SS2") (pinfunction "SS2_SS2") (pintype "bidirectional"))
    )
    (net (code "10") (name "GPIO0") (class "Default")
      (node (ref "IC4") (pin "18") (pinfunction "GPIO0_18") (pintype "bidirectional"))
      (node (ref "IC5") (pin "8") (pinfunction "PB9/EIC/AIN3/SCOM4PAD1//TC4_8") (pintype "bidirectional"))
    )
    (net (code "11") (name "I2S_FS") (class "Default")
      (node (ref "CONN_DATA") (pin "12") (pinfunction "12_12") (pintype "passive"))
      (node (ref "IC5") (pin "16") (pinfunction "PA11/EIC/AIN19/SCOM2PAD3+/TC1_16") (pintype "bidirectional"))
    )
    (net (code "12") (name "I2S_SCK") (class "Default")
      (node (ref "CONN_DATA") (pin "8") (pinfunction "8_8") (pintype "passive"))
      (node (ref "IC5") (pin "15") (pinfunction "PA10/EIC/AIN18/SCOM2PAD2+/TC1_15") (pintype "bidirectional"))
    )
    (net (code "13") (name "I2S_SD") (class "Default")
      (node (ref "CONN_DATA") (pin "10") (pinfunction "10_10") (pintype "passive"))
      (node (ref "IC5") (pin "12") (pinfunction "PA7/EIC/AIN7/SCOM0PAD3/TC1_12") (pintype "bidirectional"))
    )
    (net (code "14") (name "INT_CHG") (class "Default")
      (node (ref "IC2") (pin "7") (pinfunction "INT_7") (pintype "bidirectional"))
      (node (ref "IC5") (pin "4") (pinfunction "PA3/EIC/REF/AIN1_4") (pintype "bidirectional"))
      (node (ref "R30") (pin "1") (pinfunction "1_1") (pintype "passive"))
    )
    (net (code "15") (name "LED_BLUE") (class "Default")
      (node (ref "IC5") (pin "27") (pinfunction "PA18/EIC/SCOM1PAD2+/TC3_27") (pintype "bidirectional"))
      (node (ref "R21") (pin "1") (pinfunction "1_1") (pintype "passive"))
    )
    (net (code "16") (name "LED_GREEN") (class "Default")
      (node (ref "IC5") (pin "28") (pinfunction "PA19/EIC/SCOM1PAD3+/TC3_28") (pintype "bidirectional"))
      (node (ref "R20") (pin "1") (pinfunction "1_1") (pintype "passive"))
    )
    (net (code "17") (name "LED_RED") (class "Default")
      (node (ref "IC5") (pin "29") (pinfunction "PA20/EIC/SCOM5PAD2+_29") (pintype "bidirectional"))
      (node (ref "R19") (pin "1") (pinfunction "1_1") (pintype "passive"))
    )
    (net (code "18") (name "MISO") (class "Default")
      (node (ref "IC5") (pin "21") (pinfunction "PA12/I2C/EIC/SCOM2PAD0+/TC2_21") (pintype "bidirectional"))
      (node (ref "IC6") (pin "2") (pinfunction "SO/IO1_2") (pintype "bidirectional"))
      (node (ref "SD1") (pin "7") (pinfunction "DO/DAT0_7") (pintype "bidirectional"))
    )
    (net (code "19") (name "MOSI") (class "Default")
      (node (ref "IC5") (pin "19") (pinfunction "PB10/EIC/SCOM4PAD2/TC5_19") (pintype "bidirectional"))
      (node (ref "IC6") (pin "5") (pinfunction "SI/IO0_5") (pintype "bidirectional"))
      (node (ref "SD1") (pin "3") (pinfunction "DI/CMD_3") (pintype "bidirectional"))
    )
    (net (code "20") (name "M_BAT") (class "Default")
      (node (ref "IC5") (pin "3") (pinfunction "PA2/EIC/AIN0_3") (pintype "bidirectional"))
      (node (ref "R12") (pin "2") (pinfunction "2_2") (pintype "passive"))
      (node (ref "R2") (pin "1") (pinfunction "1_1") (pintype "passive"))
    )
    (net (code "21") (name "Net-(C14-Pad2)") (class "Default")
      (node (ref "C14") (pin "2") (pinfunction "2_2") (pintype "passive"))
      (node (ref "IC2") (pin "19") (pinfunction "SW_19") (pintype "bidirectional"))
      (node (ref "IC2") (pin "20") (pinfunction "SW_20") (pintype "bidirectional"))
      (node (ref "L2") (pin "1") (pinfunction "1_1") (pintype "bidirectional"))
    )
    (net (code "22") (name "Net-(IC1-SW)") (class "Default")
      (node (ref "C21") (pin "2") (pinfunction "2_2") (pintype "passive"))
      (node (ref "IC1") (pin "5") (pinfunction "SW_5") (pintype "bidirectional"))
      (node (ref "L7") (pin "P$2") (pinfunction "P$2_P$2") (pintype "bidirectional"))
    )
    (net (code "23") (name "Net-(IC2-BTST)") (class "Default")
      (node (ref "C14") (pin "1") (pinfunction "1_1") (pintype "passive"))
      (node (ref "IC2") (pin "21") (pinfunction "BTST_21") (pintype "bidirectional"))
    )
    (net (code "24") (name "Net-(IC2-OTG)") (class "Default")
      (node (ref "IC2") (pin "8") (pinfunction "OTG_8") (pintype "bidirectional"))
      (node (ref "Q2") (pin "3") (pinfunction "D_3") (pintype "passive"))
      (node (ref "R8") (pin "1") (pinfunction "1_1") (pintype "passive"))
    )
    (net (code "25") (name "Net-(IC2-PMID)") (class "Default")
      (node (ref "C12") (pin "2") (pinfunction "2_2") (pintype "passive"))
      (node (ref "C13") (pin "2") (pinfunction "2_2") (pintype "passive"))
      (node (ref "IC2") (pin "23") (pinfunction "PMID_23") (pintype "bidirectional"))
    )
    (net (code "26") (name "Net-(IC2-PSEL)") (class "Default")
      (node (ref "IC2") (pin "2") (pinfunction "PSEL_2") (pintype "bidirectional"))
      (node (ref "R6") (pin "2") (pinfunction "2_2") (pintype "passive"))
    )
    (net (code "27") (name "Net-(IC2-REGN)") (class "Default")
      (node (ref "C17") (pin "2") (pinfunction "2_2") (pintype "passive"))
      (node (ref "IC2") (pin "22") (pinfunction "REGN_22") (pintype "bidirectional"))
      (node (ref "R10") (pin "2") (pinfunction "2_2") (pintype "passive"))
    )
    (net (code "28") (name "Net-(IC2-TS)") (class "Default")
      (node (ref "IC2") (pin "11") (pinfunction "TS_11") (pintype "bidirectional"))
      (node (ref "R1") (pin "2") (pinfunction "2_2") (pintype "passive"))
      (node (ref "R10") (pin "1") (pinfunction "1_1") (pintype "passive"))
      (node (ref "R11") (pin "2") (pinfunction "2_2") (pintype "passive"))
    )
    (net (code "29") (name "Net-(IC2-{slash}CE)") (class "Default")
      (node (ref "IC2") (pin "9") (pinfunction "/CE_9") (pintype "bidirectional"))
      (node (ref "R9") (pin "2") (pinfunction "2_2") (pintype "passive"))
    )
    (net (code "30") (name "Net-(IC3-EN)") (class "Default")
      (node (ref "IC3") (pin "5") (pinfunction "EN_5") (pintype "bidirectional"))
      (node (ref "R5") (pin "2") (pinfunction "2_2") (pintype "passive"))
    )
    (net (code "31") (name "Net-(IC3-OUT)") (class "Default")
      (node (ref "F2") (pin "2") (pinfunction "2_2") (pintype "passive"))
      (node (ref "IC3") (pin "1") (pinfunction "OUT_1") (pintype "bidirectional"))
      (node (ref "IC3") (pin "2") (pinfunction "SENSE_2") (pintype "bidirectional"))
    )
    (net (code "32") (name "Net-(IC4-CS0)") (class "Default")
      (node (ref "IC4") (pin "9") (pinfunction "CS0_9") (pintype "input"))
      (node (ref "R3") (pin "1") (pinfunction "1_1") (pintype "passive"))
    )
    (net (code "33") (name "Net-(IC4-GND)") (class "Default")
      (node (ref "C1") (pin "1") (pinfunction "1_1") (pintype "passive"))
      (node (ref "IC4") (pin "15") (pinfunction "GND_15") (pintype "power_in"))
      (node (ref "IC4") (pin "16") (pinfunction "GPIO15_16") (pintype "bidirectional"))
      (node (ref "IC4") (pin "20") (pinfunction "GPIO4_20") (pintype "bidirectional"))
      (node (ref "L4") (pin "1") (pinfunction "1_1") (pintype "passive"))
    )
    (net (code "34") (name "Net-(IC5-PA0{slash}XIN32{slash}EIC{slash}SCOM1PAD0{slash}TC2)") (class "Default")
      (node (ref "C19") (pin "2") (pinfunction "2_2") (pintype "passive"))
      (node (ref "IC5") (pin "1") (pinfunction "PA0/XIN32/EIC/SCOM1PAD0/TC2_1") (pintype "bidirectional"))
      (node (ref "Y1") (pin "2") (pinfunction "2_2") (pintype "passive"))
    )
    (net (code "35") (name "Net-(IC5-PA1{slash}XOUT32{slash}EIC{slash}SCOM1PAD1{slash}TC2)") (class "Default")
      (node (ref "C20") (pin "2") (pinfunction "2_2") (pintype "passive"))
      (node (ref "IC5") (pin "2") (pinfunction "PA1/XOUT32/EIC/SCOM1PAD1/TC2_2") (pintype "bidirectional"))
      (node (ref "Y1") (pin "1") (pinfunction "1_1") (pintype "passive"))
    )
    (net (code "36") (name "Net-(IC5-VDDANA)") (class "Default")
      (node (ref "C22") (pin "2") (pinfunction "2_2") (pintype "passive"))
      (node (ref "IC5") (pin "6") (pinfunction "VDDANA_6") (pintype "power_in"))
      (node (ref "L5") (pin "2") (pinfunction "2_2") (pintype "passive"))
    )
    (net (code "37") (name "Net-(IC5-VDDCORE1)") (class "Default")
      (node (ref "C26") (pin "2") (pinfunction "2_2") (pintype "passive"))
      (node (ref "IC5") (pin "43") (pinfunction "VDDCORE1_43") (pintype "input"))
    )
    (net (code "38") (name "Net-(L3-Pad2)") (class "Default")
      (node (ref "L3") (pin "2") (pinfunction "2_2") (pintype "passive"))
      (node (ref "Q1") (pin "3") (pinfunction "D_3") (pintype "passive"))
      (node (ref "Q1") (pin "6") (pinfunction "D_6") (pintype "passive"))
      (node (ref "Q1") (pin "TP1") (pinfunction "D_TP1") (pintype "passive"))
      (node (ref "Q1") (pin "TP2") (pinfunction "D_TP2") (pintype "passive"))
    )
    (net (code "39") (name "Net-(LED1-BLUE)") (class "Default")
      (node (ref "LED1") (pin "3") (pinfunction "BLUE_3") (pintype "passive"))
      (node (ref "R21") (pin "2") (pinfunction "2_2") (pintype "passive"))
    )
    (net (code "40") (name "Net-(LED1-GREEN)") (class "Default")
      (node (ref "LED1") (pin "2") (pinfunction "GREEN_2") (pintype "passive"))
      (node (ref "R20") (pin "2") (pinfunction "2_2") (pintype "passive"))
    )
    (net (code "41") (name "Net-(LED1-RED)") (class "Default")
      (node (ref "LED1") (pin "1") (pinfunction "RED_1") (pintype "passive"))
      (node (ref "R19") (pin "2") (pinfunction "2_2") (pintype "passive"))
    )
    (net (code "42") (name "Net-(LED2-Pad-)") (class "Default")
      (node (ref "LED2") (pin "-") (pinfunction "-_-") (pintype "passive"))
      (node (ref "R18") (pin "2") (pinfunction "2_2") (pintype "passive"))
    )
    (net (code "43") (name "Net-(LED3-Pad-)") (class "Default")
      (node (ref "LED3") (pin "-") (pinfunction "-_-") (pintype "passive"))
      (node (ref "R4") (pin "2") (pinfunction "2_2") (pintype "passive"))
    )
    (net (code "44") (name "Net-(Q3A-S)") (class "Default")
      (node (ref "C8") (pin "2") (pinfunction "2_2") (pintype "passive"))
      (node (ref "F1") (pin "1") (pinfunction "1_1") (pintype "passive"))
      (node (ref "Q3") (pin "1") (pinfunction "S_1") (pintype "passive"))
      (node (ref "Q3") (pin "4") (pinfunction "S_4") (pintype "passive"))
      (node (ref "R29") (pin "1") (pinfunction "1_1") (pintype "passive"))
    )
    (net (code "45") (name "Net-(TVS1-VBUS)") (class "Default")
      (node (ref "L1") (pin "1") (pinfunction "1_1") (pintype "passive"))
      (node (ref "TVS1") (pin "6") (pinfunction "VBUS_6") (pintype "passive"))
      (node (ref "USB") (pin "1") (pinfunction "VBUS_1") (pintype "power_in"))
    )
    (net (code "46") (name "PA30_SWCLK") (class "Default")
      (node (ref "IC5") (pin "45") (pinfunction "PA30/EIC/SCOM1PAD2/TC1_45") (pintype "bidirectional"))
      (node (ref "SWD") (pin "4") (pinfunction "4_4") (pintype "passive"))
    )
    (net (code "47") (name "PA31_SWDIO") (class "Default")
      (node (ref "IC5") (pin "46") (pinfunction "PA31/EIC/SCOM1PAD3/TC1_46") (pintype "bidirectional"))
      (node (ref "SWD") (pin "2") (pinfunction "2_2") (pintype "passive"))
    )
    (net (code "48") (name "RESET") (class "Default")
      (node (ref "D1") (pin "+") (pinfunction "+_+") (pintype "passive"))
      (node (ref "IC4") (pin "5") (pinfunction "GPIO14_5") (pintype "bidirectional"))
      (node (ref "P2") (pin "1") (pinfunction "A0_1") (pintype "bidirectional"))
      (node (ref "P2") (pin "2") (pinfunction "A1_2") (pintype "bidirectional"))
      (node (ref "R15") (pin "2") (pinfunction "2_2") (pintype "passive"))
      (node (ref "R16") (pin "1") (pinfunction "1_1") (pintype "passive"))
      (node (ref "SWD") (pin "10") (pinfunction "10_10") (pintype "passive"))
    )
    (net (code "49") (name "RXWIFI") (class "Default")
      (node (ref "IC4") (pin "22") (pinfunction "TXD_22") (pintype "output"))
      (node (ref "IC5") (pin "10") (pinfunction "PA5/EIC/AIN5/SCOM0PAD1/TC0_10") (pintype "bidirectional"))
    )
    (net (code "50") (name "RX_PMS") (class "Default")
      (node (ref "CONN_DATA") (pin "11") (pinfunction "11_11") (pintype "passive"))
      (node (ref "IC5") (pin "48") (pinfunction "PB3/EIC/AIN11/SCOM5PAD1_48") (pintype "bidirectional"))
    )
    (net (code "51") (name "SCK") (class "Default")
      (node (ref "IC5") (pin "20") (pinfunction "PB11/EIC/SCOM4PAD3/TC5_20") (pintype "bidirectional"))
      (node (ref "IC6") (pin "6") (pinfunction "SCK_6") (pintype "bidirectional"))
      (node (ref "SD1") (pin "5") (pinfunction "CLK_5") (pintype "bidirectional"))
    )
    (net (code "52") (name "SCL") (class "Default")
      (node (ref "CONN_DATA") (pin "4") (pinfunction "4_4") (pintype "passive"))
      (node (ref "IC2") (pin "5") (pinfunction "SCL_5") (pintype "bidirectional"))
      (node (ref "IC5") (pin "32") (pinfunction "PA23/I2C/EIC/SCOM5PAD1+/TC4_32") (pintype "bidirectional"))
      (node (ref "R14") (pin "1") (pinfunction "1_1") (pintype "passive"))
    )
    (net (code "53") (name "SCL_GROOVE") (class "Default")
      (node (ref "IC5") (pin "26") (pinfunction "PA17/I2C/EIC/SCOM1PAD1+/TC2_26") (pintype "bidirectional"))
      (node (ref "R22") (pin "1") (pinfunction "1_1") (pintype "passive"))
      (node (ref "X1") (pin "1") (pinfunction "1_1") (pintype "bidirectional"))
    )
    (net (code "54") (name "SDA") (class "Default")
      (node (ref "CONN_DATA") (pin "6") (pinfunction "6_6") (pintype "passive"))
      (node (ref "IC2") (pin "6") (pinfunction "SDA_6") (pintype "bidirectional"))
      (node (ref "IC5") (pin "31") (pinfunction "PA22/I2C/EIC/SCOM5PAD0+/TC4_31") (pintype "bidirectional"))
      (node (ref "R13") (pin "1") (pinfunction "1_1") (pintype "passive"))
    )
    (net (code "55") (name "SDA_GROOVE") (class "Default")
      (node (ref "IC5") (pin "25") (pinfunction "PA16/I2C/EIC/SCOM1PAD0+/TC2_25") (pintype "bidirectional"))
      (node (ref "R23") (pin "1") (pinfunction "1_1") (pintype "passive"))
      (node (ref "X1") (pin "2") (pinfunction "2_2") (pintype "bidirectional"))
    )
    (net (code "56") (name "SW_GROOVE") (class "Default")
      (node (ref "IC5") (pin "38") (pinfunction "PB23/EIC/SCOM5PAD3_38") (pintype "bidirectional"))
      (node (ref "Q3") (pin "2") (pinfunction "G_2") (pintype "passive"))
      (node (ref "Q3") (pin "5") (pinfunction "G_5") (pintype "passive"))
      (node (ref "R29") (pin "2") (pinfunction "2_2") (pintype "passive"))
    )
    (net (code "57") (name "SW_PMS") (class "Default")
      (node (ref "IC1") (pin "3") (pinfunction "EN_3") (pintype "bidirectional"))
      (node (ref "IC5") (pin "11") (pinfunction "PA6/EIC/AIN6/SCOM0PAD2/TC1_11") (pintype "bidirectional"))
      (node (ref "R27") (pin "2") (pinfunction "2_2") (pintype "passive"))
    )
    (net (code "58") (name "SW_WIFI") (class "Default")
      (node (ref "IC5") (pin "37") (pinfunction "PB22/EIC/SCOM5PAD2_37") (pintype "bidirectional"))
      (node (ref "Q1") (pin "2") (pinfunction "G_2") (pintype "passive"))
      (node (ref "Q1") (pin "5") (pinfunction "G_5") (pintype "passive"))
      (node (ref "R28") (pin "1") (pinfunction "1_1") (pintype "passive"))
    )
    (net (code "59") (name "TARGET_RESET") (class "Default")
      (node (ref "C3") (pin "2") (pinfunction "2_2") (pintype "passive"))
      (node (ref "IC5") (pin "40") (pinfunction "RESETN_40") (pintype "bidirectional"))
      (node (ref "R15") (pin "1") (pinfunction "1_1") (pintype "passive"))
    )
    (net (code "60") (name "TARGET_USB_N") (class "Default")
      (node (ref "IC5") (pin "33") (pinfunction "PA24/EIC/SCOM3PAD2+/TC5_33") (pintype "bidirectional"))
      (node (ref "TVS1") (pin "2") (pinfunction "D-_2") (pintype "passive"))
      (node (ref "USB") (pin "2") (pinfunction "D-_2") (pintype "bidirectional"))
    )
    (net (code "61") (name "TARGET_USB_P") (class "Default")
      (node (ref "IC5") (pin "34") (pinfunction "PA25/EIC/SCOM3PAD3+/TC5_34") (pintype "bidirectional"))
      (node (ref "TVS1") (pin "1") (pinfunction "D+_1") (pintype "passive"))
      (node (ref "USB") (pin "3") (pinfunction "D+_3") (pintype "bidirectional"))
    )
    (net (code "62") (name "TXLED") (class "Default")
      (node (ref "IC5") (pin "39") (pinfunction "PA27/EIC_39") (pintype "bidirectional"))
      (node (ref "R18") (pin "1") (pinfunction "1_1") (pintype "passive"))
    )
    (net (code "63") (name "TXWIFI") (class "Default")
      (node (ref "IC4") (pin "21") (pinfunction "RXD_21") (pintype "input"))
      (node (ref "IC5") (pin "9") (pinfunction "PA4/EIC/REF/AIN4/SCOM0PAD0/TC0_9") (pintype "bidirectional"))
    )
    (net (code "64") (name "TX_PMS") (class "Default")
      (node (ref "CONN_DATA") (pin "13") (pinfunction "13_13") (pintype "passive"))
      (node (ref "IC5") (pin "47") (pinfunction "PB2/EIC/AIN10/SCOM5PAD0_47") (pintype "bidirectional"))
    )
    (net (code "65") (name "USB_ID") (class "Default")
      (node (ref "Q2") (pin "2") (pinfunction "G_2") (pintype "passive"))
      (node (ref "R26") (pin "1") (pinfunction "1_1") (pintype "passive"))
      (node (ref "R7") (pin "2") (pinfunction "2_2") (pintype "passive"))
      (node (ref "TVS1") (pin "3") (pinfunction "ID_3") (pintype "passive"))
      (node (ref "USB") (pin "4") (pinfunction "ID_4") (pintype "bidirectional"))
    )
    (net (code "66") (name "VBAT") (class "Default")
      (node (ref "BAT") (pin "+") (pinfunction "1_+") (pintype "bidirectional"))
      (node (ref "C28") (pin "2") (pinfunction "2_2") (pintype "passive"))
      (node (ref "IC2") (pin "13") (pinfunction "VBAT_13") (pintype "bidirectional"))
      (node (ref "IC2") (pin "14") (pinfunction "VBAT_14") (pintype "bidirectional"))
    )
    (net (code "67") (name "VCC") (class "Default")
      (node (ref "C2") (pin "2") (pinfunction "2_2") (pintype "passive"))
      (node (ref "C23") (pin "2") (pinfunction "2_2") (pintype "passive"))
      (node (ref "C24") (pin "2") (pinfunction "2_2") (pintype "passive"))
      (node (ref "C25") (pin "2") (pinfunction "2_2") (pintype "passive"))
      (node (ref "C9") (pin "2") (pinfunction "2_2") (pintype "passive"))
      (node (ref "CONN_DATA") (pin "1") (pinfunction "1_1") (pintype "passive"))
      (node (ref "CONN_DATA") (pin "2") (pinfunction "2_2") (pintype "passive"))
      (node (ref "D1") (pin "-") (pinfunction "-_-") (pintype "passive"))
      (node (ref "F1") (pin "2") (pinfunction "2_2") (pintype "passive"))
      (node (ref "F2") (pin "1") (pinfunction "1_1") (pintype "passive"))
      (node (ref "IC5") (pin "17") (pinfunction "VDDIO1_17") (pintype "power_in"))
      (node (ref "IC5") (pin "36") (pinfunction "VDDIO2_36") (pintype "power_in"))
      (node (ref "IC5") (pin "44") (pinfunction "VDDIN_44") (pintype "power_in"))
      (node (ref "IC6") (pin "8") (pinfunction "VCC_8") (pintype "bidirectional"))
      (node (ref "L5") (pin "1") (pinfunction "1_1") (pintype "passive"))
      (node (ref "LED1") (pin "4") (pinfunction "A_4") (pintype "passive"))
      (node (ref "LED2") (pin "+") (pinfunction "+_+") (pintype "passive"))
      (node (ref "LED3") (pin "+") (pinfunction "+_+") (pintype "passive"))
      (node (ref "Q1") (pin "1") (pinfunction "S_1") (pintype "passive"))
      (node (ref "Q1") (pin "4") (pinfunction "S_4") (pintype "passive"))
      (node (ref "R13") (pin "2") (pinfunction "2_2") (pintype "passive"))
      (node (ref "R14") (pin "2") (pinfunction "2_2") (pintype "passive"))
      (node (ref "R16") (pin "2") (pinfunction "2_2") (pintype "passive"))
      (node (ref "R17") (pin "2") (pinfunction "2_2") (pintype "passive"))
      (node (ref "R24") (pin "2") (pinfunction "2_2") (pintype "passive"))
      (node (ref "R25") (pin "2") (pinfunction "2_2") (pintype "passive"))
      (node (ref "R26") (pin "2") (pinfunction "2_2") (pintype "passive"))
      (node (ref "R28") (pin "2") (pinfunction "2_2") (pintype "passive"))
      (node (ref "R30") (pin "2") (pinfunction "2_2") (pintype "passive"))
      (node (ref "R8") (pin "2") (pinfunction "2_2") (pintype "passive"))
      (node (ref "SD1") (pin "4") (pinfunction "VCC_4") (pintype "bidirectional"))
      (node (ref "SWD") (pin "1") (pinfunction "1_1") (pintype "passive"))
    )
    (net (code "68") (name "VCC_GROOVE") (class "Default")
      (node (ref "Q3") (pin "3") (pinfunction "D_3") (pintype "passive"))
      (node (ref "Q3") (pin "6") (pinfunction "D_6") (pintype "passive"))
      (node (ref "Q3") (pin "TP1") (pinfunction "D_TP1") (pintype "passive"))
      (node (ref "Q3") (pin "TP2") (pinfunction "D_TP2") (pintype "passive"))
      (node (ref "R22") (pin "2") (pinfunction "2_2") (pintype "passive"))
      (node (ref "R23") (pin "2") (pinfunction "2_2") (pintype "passive"))
      (node (ref "X1") (pin "3") (pinfunction "3_3") (pintype "bidirectional"))
    )
    (net (code "69") (name "VCC_WIFI") (class "Default")
      (node (ref "C1") (pin "2") (pinfunction "2_2") (pintype "passive"))
      (node (ref "IC4") (pin "1") (pinfunction "RESET_1") (pintype "input"))
      (node (ref "IC4") (pin "17") (pinfunction "GPIO2_17") (pintype "bidirectional"))
      (node (ref "IC4") (pin "8") (pinfunction "VCC_8") (pintype "power_in"))
      (node (ref "L3") (pin "1") (pinfunction "1_1") (pintype "passive"))
      (node (ref "R3") (pin "2") (pinfunction "2_2") (pintype "passive"))
    )
    (net (code "70") (name "VSYS") (class "Default")
      (node (ref "C10") (pin "2") (pinfunction "2_2") (pintype "passive"))
      (node (ref "C11") (pin "2") (pinfunction "2_2") (pintype "passive"))
      (node (ref "C15") (pin "2") (pinfunction "2_2") (pintype "passive"))
      (node (ref "C16") (pin "2") (pinfunction "2_2") (pintype "passive"))
      (node (ref "C18") (pin "2") (pinfunction "2_2") (pintype "passive"))
      (node (ref "IC1") (pin "4") (pinfunction "IN_4") (pintype "bidirectional"))
      (node (ref "IC2") (pin "15") (pinfunction "SYS_15") (pintype "bidirectional"))
      (node (ref "IC2") (pin "16") (pinfunction "SYS_16") (pintype "bidirectional"))
      (node (ref "IC3") (pin "6") (pinfunction "IN_6") (pintype "bidirectional"))
      (node (ref "L2") (pin "2") (pinfunction "2_2") (pintype "bidirectional"))
      (node (ref "L7") (pin "P$1") (pinfunction "P$1_P$1") (pintype "bidirectional"))
      (node (ref "R2") (pin "2") (pinfunction "2_2") (pintype "passive"))
      (node (ref "R5") (pin "1") (pinfunction "1_1") (pintype "passive"))
    )
    (net (code "71") (name "VUSB") (class "Default")
      (node (ref "C4") (pin "2") (pinfunction "2_2") (pintype "passive"))
      (node (ref "C5") (pin "2") (pinfunction "2_2") (pintype "passive"))
      (node (ref "C6") (pin "2") (pinfunction "2_2") (pintype "passive"))
      (node (ref "IC2") (pin "1") (pinfunction "VBUS_1") (pintype "bidirectional"))
      (node (ref "IC2") (pin "24") (pinfunction "VBUS_24") (pintype "bidirectional"))
      (node (ref "L1") (pin "2") (pinfunction "2_2") (pintype "passive"))
    )
    (net (code "72") (name "WIFI_LED") (class "Default")
      (node (ref "IC4") (pin "19") (pinfunction "GPIO5_19") (pintype "bidirectional"))
      (node (ref "R4") (pin "1") (pinfunction "1_1") (pintype "passive"))
    )
    (net (code "73") (name "unconnected-(IC2-QON-Pad12)") (class "Default")
      (node (ref "IC2") (pin "12") (pinfunction "QON_12") (pintype "bidirectional"))
    )
    (net (code "74") (name "unconnected-(IC2-STAT-Pad4)") (class "Default")
      (node (ref "IC2") (pin "4") (pinfunction "STAT_4") (pintype "bidirectional"))
    )
    (net (code "75") (name "unconnected-(IC2-{slash}PG-Pad3)") (class "Default")
      (node (ref "IC2") (pin "3") (pinfunction "/PG_3") (pintype "bidirectional"))
    )
    (net (code "76") (name "unconnected-(IC3-PG-Pad4)") (class "Default")
      (node (ref "IC3") (pin "4") (pinfunction "PG_4") (pintype "bidirectional"))
    )
    (net (code "77") (name "unconnected-(IC4-ADC-Pad2)") (class "Default")
      (node (ref "IC4") (pin "2") (pinfunction "ADC_2") (pintype "passive"))
    )
    (net (code "78") (name "unconnected-(IC4-GPIO9-Pad11)") (class "Default")
      (node (ref "IC4") (pin "11") (pinfunction "GPIO9_11") (pintype "bidirectional"))
    )
    (net (code "79") (name "unconnected-(IC4-GPIO10-Pad12)") (class "Default")
      (node (ref "IC4") (pin "12") (pinfunction "GPIO10_12") (pintype "bidirectional"))
    )
    (net (code "80") (name "unconnected-(IC4-GPIO12-Pad6)") (class "Default")
      (node (ref "IC4") (pin "6") (pinfunction "GPIO12_6") (pintype "bidirectional"))
    )
    (net (code "81") (name "unconnected-(IC4-GPIO13-Pad7)") (class "Default")
      (node (ref "IC4") (pin "7") (pinfunction "GPIO13_7") (pintype "bidirectional"))
    )
    (net (code "82") (name "unconnected-(IC4-GPIO16-Pad4)") (class "Default")
      (node (ref "IC4") (pin "4") (pinfunction "GPIO16_4") (pintype "bidirectional"))
    )
    (net (code "83") (name "unconnected-(IC4-MISO-Pad10)") (class "Default")
      (node (ref "IC4") (pin "10") (pinfunction "MISO_10") (pintype "passive"))
    )
    (net (code "84") (name "unconnected-(IC4-MOSI-Pad13)") (class "Default")
      (node (ref "IC4") (pin "13") (pinfunction "MOSI_13") (pintype "bidirectional"))
    )
    (net (code "85") (name "unconnected-(IC4-SCLK-Pad14)") (class "Default")
      (node (ref "IC4") (pin "14") (pinfunction "SCLK_14") (pintype "bidirectional"))
    )
    (net (code "86") (name "unconnected-(IC6-IO3{slash}RESET#-Pad7)") (class "Default")
      (node (ref "IC6") (pin "7") (pinfunction "IO3/RESET#_7") (pintype "bidirectional"))
    )
    (net (code "87") (name "unconnected-(IC6-WP#{slash}IO2-Pad3)") (class "Default")
      (node (ref "IC6") (pin "3") (pinfunction "WP#/IO2_3") (pintype "bidirectional"))
    )
    (net (code "88") (name "unconnected-(SD1-DAT1-Pad8)") (class "Default")
      (node (ref "SD1") (pin "8") (pinfunction "DAT1_8") (pintype "bidirectional"))
    )
    (net (code "89") (name "unconnected-(SD1-DAT2-Pad1)") (class "Default")
      (node (ref "SD1") (pin "1") (pinfunction "DAT2_1") (pintype "bidirectional"))
    )
    (net (code "90") (name "unconnected-(SWD-Pad6)") (class "Default")
      (node (ref "SWD") (pin "6") (pinfunction "6_6") (pintype "passive"))
    )
    (net (code "91") (name "unconnected-(SWD-Pad7)") (class "Default")
      (node (ref "SWD") (pin "7") (pinfunction "7_7") (pintype "passive"))
    )
    (net (code "92") (name "unconnected-(SWD-Pad8)") (class "Default")
      (node (ref "SWD") (pin "8") (pinfunction "8_8") (pintype "passive"))
    )
    (net (code "93") (name "unconnected-(TVS1-N.C.-Pad5)") (class "Default")
      (node (ref "TVS1") (pin "5") (pinfunction "N.C._5") (pintype "passive"))
    )
    (net (code "94") (name "~{INT_CCS}") (class "Default")
      (node (ref "CONN_DATA") (pin "5") (pinfunction "5_5") (pintype "passive"))
      (node (ref "IC5") (pin "13") (pinfunction "PA8/I2C/AIN16/SCOM2PAD0+/TC0_13") (pintype "bidirectional"))
    )
    (net (code "95") (name "~{WAKE_CCS}") (class "Default")
      (node (ref "CONN_DATA") (pin "7") (pinfunction "7_7") (pintype "passive"))
      (node (ref "IC5") (pin "41") (pinfunction "PA28/EIC_41") (pintype "bidirectional"))
    )
  )
)
